# FOTA_LED_Driver.net
KiCad netlist of a schematic drawn in Altium Designer
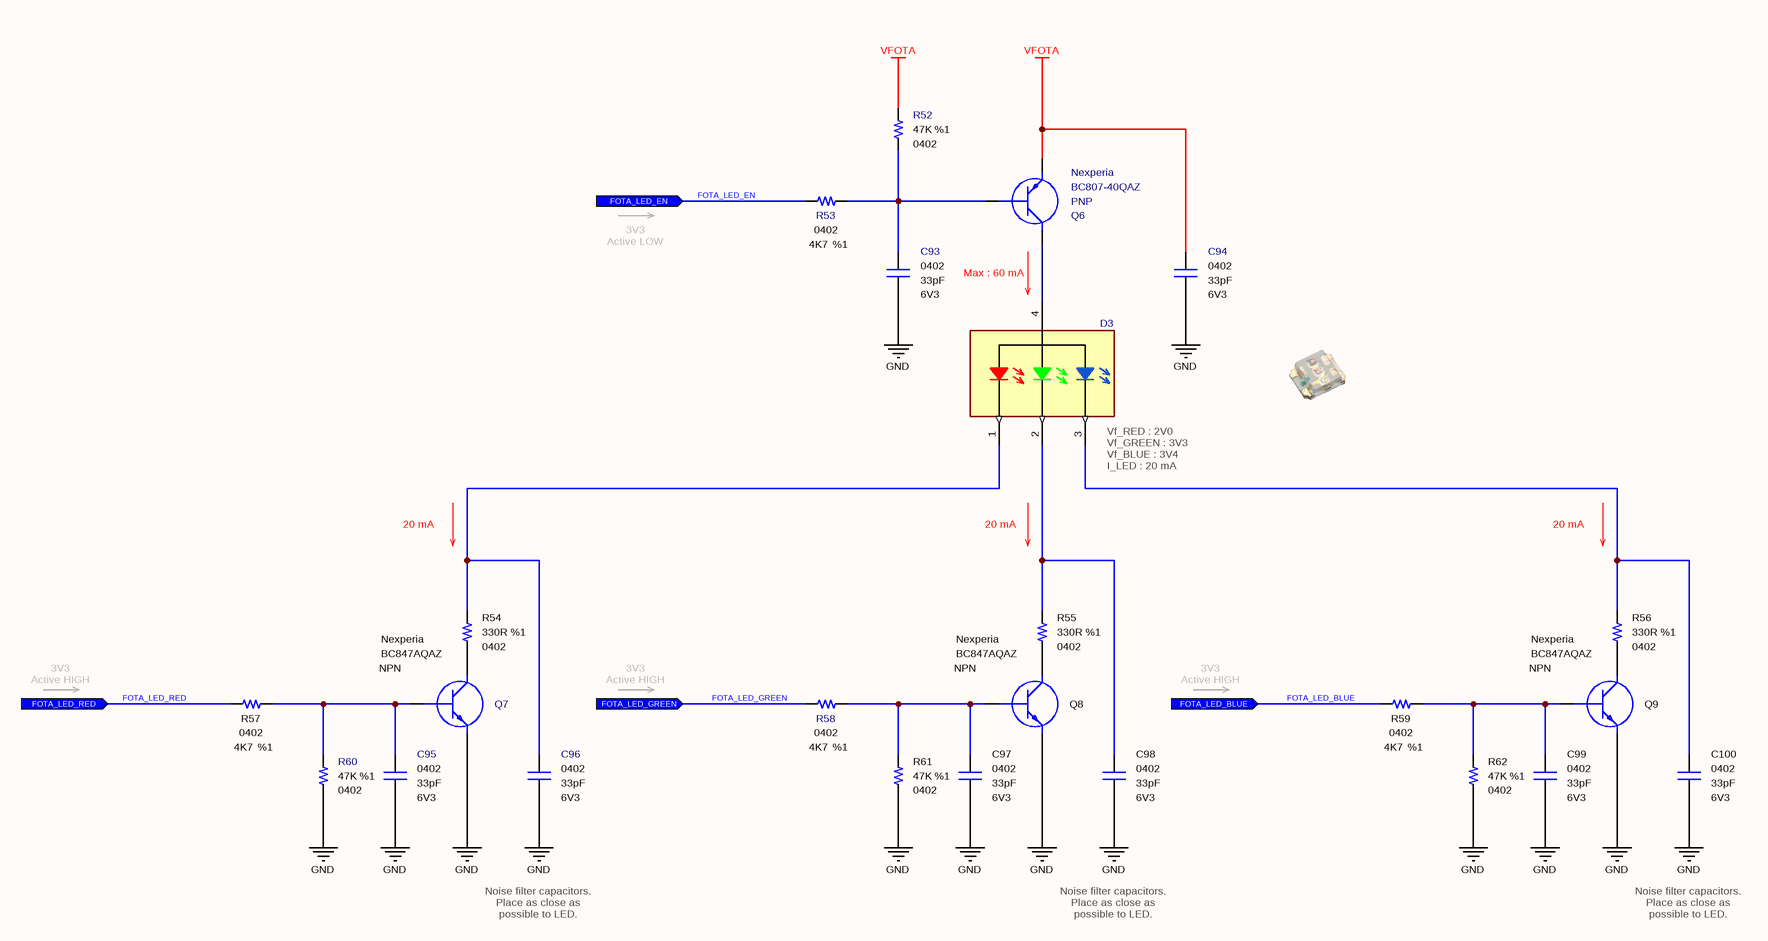
[diagram p0: FOTA LED Driver.SchDoc]

(export (version "E")
  (design (tool "Eeschema 10.0.6"))
  (components
    (comp (ref "C93")
      (value "33pF")
      (footprint "CAPACITOR_0402")
      (description "Capacitor - 33pF [0402] (Ceramic)")
      (fields
        (field (name "CASE") "0402")
        (field (name "TOLERANCE") "10%")
        (field (name "VOLTAGE") "6V3")
        (field (name "MANUFACTURER PART NUMBER") "C0402C330J9RACAUTO")
      )
      (libsource (lib "Ovoo_Library") (part "Capacitor - 33pF [0402-6V3]"))
    )
    (comp (ref "C94")
      (value "33pF")
      (footprint "CAPACITOR_0402")
      (description "Capacitor - 33pF [0402] (Ceramic)")
      (fields
        (field (name "CASE") "0402")
        (field (name "TOLERANCE") "10%")
        (field (name "VOLTAGE") "6V3")
        (field (name "MANUFACTURER PART NUMBER") "C0402C330J9RACAUTO")
      )
      (libsource (lib "Ovoo_Library") (part "Capacitor - 33pF [0402-6V3]"))
    )
    (comp (ref "C95")
      (value "33pF")
      (footprint "CAPACITOR_0402")
      (description "Capacitor - 33pF [0402] (Ceramic)")
      (fields
        (field (name "CASE") "0402")
        (field (name "TOLERANCE") "10%")
        (field (name "VOLTAGE") "6V3")
        (field (name "MANUFACTURER PART NUMBER") "C0402C330J9RACAUTO")
      )
      (libsource (lib "Ovoo_Library") (part "Capacitor - 33pF [0402-6V3]"))
    )
    (comp (ref "C96")
      (value "33pF")
      (footprint "CAPACITOR_0402")
      (description "Capacitor - 33pF [0402] (Ceramic)")
      (fields
        (field (name "CASE") "0402")
        (field (name "TOLERANCE") "10%")
        (field (name "VOLTAGE") "6V3")
        (field (name "MANUFACTURER PART NUMBER") "C0402C330J9RACAUTO")
      )
      (libsource (lib "Ovoo_Library") (part "Capacitor - 33pF [0402-6V3]"))
    )
    (comp (ref "C97")
      (value "33pF")
      (footprint "CAPACITOR_0402")
      (description "Capacitor - 33pF [0402] (Ceramic)")
      (fields
        (field (name "CASE") "0402")
        (field (name "TOLERANCE") "10%")
        (field (name "VOLTAGE") "6V3")
        (field (name "MANUFACTURER PART NUMBER") "C0402C330J9RACAUTO")
      )
      (libsource (lib "Ovoo_Library") (part "Capacitor - 33pF [0402-6V3]"))
    )
    (comp (ref "C98")
      (value "33pF")
      (footprint "CAPACITOR_0402")
      (description "Capacitor - 33pF [0402] (Ceramic)")
      (fields
        (field (name "CASE") "0402")
        (field (name "TOLERANCE") "10%")
        (field (name "VOLTAGE") "6V3")
        (field (name "MANUFACTURER PART NUMBER") "C0402C330J9RACAUTO")
      )
      (libsource (lib "Ovoo_Library") (part "Capacitor - 33pF [0402-6V3]"))
    )
    (comp (ref "C99")
      (value "33pF")
      (footprint "CAPACITOR_0402")
      (description "Capacitor - 33pF [0402] (Ceramic)")
      (fields
        (field (name "CASE") "0402")
        (field (name "TOLERANCE") "10%")
        (field (name "VOLTAGE") "6V3")
        (field (name "MANUFACTURER PART NUMBER") "C0402C330J9RACAUTO")
      )
      (libsource (lib "Ovoo_Library") (part "Capacitor - 33pF [0402-6V3]"))
    )
    (comp (ref "C100")
      (value "33pF")
      (footprint "CAPACITOR_0402")
      (description "Capacitor - 33pF [0402] (Ceramic)")
      (fields
        (field (name "CASE") "0402")
        (field (name "TOLERANCE") "10%")
        (field (name "VOLTAGE") "6V3")
        (field (name "MANUFACTURER PART NUMBER") "C0402C330J9RACAUTO")
      )
      (libsource (lib "Ovoo_Library") (part "Capacitor - 33pF [0402-6V3]"))
    )
    (comp (ref "D3")
      (value "150066M153000")
      (footprint "Wurth_0606")
      (description "Standard LEDs - SMD PICOLED series Red LED")
      (fields (field (name "MOUSER PART NUMBER") "710-150066M153000"))
      (libsource (lib "Ovoo_Library") (part "Diode - RGB LED (150066M153000)"))
    )
    (comp (ref "Q6")
      (value "Bipolar PNP Transistors")
      (footprint "SOT1215")
      (description "Bipolar Transistors - BJT 45 V, 500 mA PNP gen purpose transistors")
      (fields
        (field (name "MOUSER PART NUMBER") "771-BC807-40QAZ")
        (field (name "POLARITY") "PNP")
        (field (name "MANUFACTURER NAME") "Nexperia")
        (field (name "MANUFACTURER PART NUMBER") "BC807-40QAZ")
      )
      (libsource (lib "Ovoo_Library") (part "Transistor - BC807"))
    )
    (comp (ref "Q7")
      (value "BC847AQAZ")
      (footprint "SOT1215")
      (description "Bipolar NPN Transistors")
      (fields
        (field (name "POLARITY") "NPN")
        (field (name "MANUFACTURER NAME") "Nexperia")
        (field (name "MANUFACTURER PART NUMBER") "BC847AQAZ")
      )
      (libsource (lib "Ovoo_Library") (part "Transistor - BC847"))
    )
    (comp (ref "Q8")
      (value "BC847AQAZ")
      (footprint "SOT1215")
      (description "Bipolar NPN Transistors")
      (fields
        (field (name "POLARITY") "NPN")
        (field (name "MANUFACTURER NAME") "Nexperia")
        (field (name "MANUFACTURER PART NUMBER") "BC847AQAZ")
      )
      (libsource (lib "Ovoo_Library") (part "Transistor - BC847"))
    )
    (comp (ref "Q9")
      (value "BC847AQAZ")
      (footprint "SOT1215")
      (description "Bipolar NPN Transistors")
      (fields
        (field (name "POLARITY") "NPN")
        (field (name "MANUFACTURER NAME") "Nexperia")
        (field (name "MANUFACTURER PART NUMBER") "BC847AQAZ")
      )
      (libsource (lib "Ovoo_Library") (part "Transistor - BC847"))
    )
    (comp (ref "R52")
      (value "47K")
      (footprint "RESISTOR_0402")
      (description "Thick Film Resistors - SMD 1/16 W 47 Kohms 1%")
      (fields
        (field (name "TOLERANCE") "%1")
        (field (name "CASE") "0402")
        (field (name "MANUFACTURER PART NUMBER") "CRCW040247K0FKED")
        (field (name "Comment") "47K - 0402 - %1 - 1/16W")
      )
      (libsource (lib "Ovoo_Library") (part "Resistor - 47K"))
    )
    (comp (ref "R53")
      (value "4K7")
      (footprint "RESISTOR_0402")
      (description "Thick Film Resistors - SMD 1/16 W 4.7 Kohms 1%")
      (fields
        (field (name "MANUFACTURER PART NUMBER") "CRCW04024K70FKED")
        (field (name "MOUSER PART NUMBER") "71-CRCW0402-4.7K-E3")
        (field (name "TOLERANCE") "%1")
        (field (name "CASE") "0402")
      )
      (libsource (lib "Ovoo_Library") (part "Resistor - 4K7"))
    )
    (comp (ref "R54")
      (value "330R")
      (footprint "RESISTOR_0402")
      (description "Thick Film Resistors - SMD 1/16 W 330 Ohm 1%")
      (fields
        (field (name "MANUFACTURER PART NUMBER") "CRCW0402330RFKED")
        (field (name "MOUSER PART NUMBER") "71-CRCW0402-330-E3")
        (field (name "CASE") "0402")
        (field (name "TOLERANCE") "%1")
      )
      (libsource (lib "Ovoo_Library") (part "Resistor - 330R"))
    )
    (comp (ref "R55")
      (value "330R")
      (footprint "RESISTOR_0402")
      (description "Thick Film Resistors - SMD 1/16 W 330 Ohm 1%")
      (fields
        (field (name "MANUFACTURER PART NUMBER") "CRCW0402330RFKED")
        (field (name "MOUSER PART NUMBER") "71-CRCW0402-330-E3")
        (field (name "CASE") "0402")
        (field (name "TOLERANCE") "%1")
      )
      (libsource (lib "Ovoo_Library") (part "Resistor - 330R"))
    )
    (comp (ref "R56")
      (value "330R")
      (footprint "RESISTOR_0402")
      (description "Thick Film Resistors - SMD 1/16 W 330 Ohm 1%")
      (fields
        (field (name "MANUFACTURER PART NUMBER") "CRCW0402330RFKED")
        (field (name "MOUSER PART NUMBER") "71-CRCW0402-330-E3")
        (field (name "CASE") "0402")
        (field (name "TOLERANCE") "%1")
      )
      (libsource (lib "Ovoo_Library") (part "Resistor - 330R"))
    )
    (comp (ref "R57")
      (value "4K7")
      (footprint "RESISTOR_0402")
      (description "Thick Film Resistors - SMD 1/16 W 4.7 Kohms 1%")
      (fields
        (field (name "MANUFACTURER PART NUMBER") "CRCW04024K70FKED")
        (field (name "MOUSER PART NUMBER") "71-CRCW0402-4.7K-E3")
        (field (name "TOLERANCE") "%1")
        (field (name "CASE") "0402")
      )
      (libsource (lib "Ovoo_Library") (part "Resistor - 4K7"))
    )
    (comp (ref "R58")
      (value "4K7")
      (footprint "RESISTOR_0402")
      (description "Thick Film Resistors - SMD 1/16 W 4.7 Kohms 1%")
      (fields
        (field (name "MANUFACTURER PART NUMBER") "CRCW04024K70FKED")
        (field (name "MOUSER PART NUMBER") "71-CRCW0402-4.7K-E3")
        (field (name "TOLERANCE") "%1")
        (field (name "CASE") "0402")
      )
      (libsource (lib "Ovoo_Library") (part "Resistor - 4K7"))
    )
    (comp (ref "R59")
      (value "4K7")
      (footprint "RESISTOR_0402")
      (description "Thick Film Resistors - SMD 1/16 W 4.7 Kohms 1%")
      (fields
        (field (name "MANUFACTURER PART NUMBER") "CRCW04024K70FKED")
        (field (name "MOUSER PART NUMBER") "71-CRCW0402-4.7K-E3")
        (field (name "TOLERANCE") "%1")
        (field (name "CASE") "0402")
      )
      (libsource (lib "Ovoo_Library") (part "Resistor - 4K7"))
    )
    (comp (ref "R60")
      (value "47K")
      (footprint "RESISTOR_0402")
      (description "Thick Film Resistors - SMD 1/16 W 47 Kohms 1%")
      (fields
        (field (name "TOLERANCE") "%1")
        (field (name "CASE") "0402")
        (field (name "MANUFACTURER PART NUMBER") "CRCW040247K0FKED")
        (field (name "Comment") "47K - 0402 - %1 - 1/16W")
      )
      (libsource (lib "Ovoo_Library") (part "Resistor - 47K"))
    )
    (comp (ref "R61")
      (value "47K")
      (footprint "RESISTOR_0402")
      (description "Thick Film Resistors - SMD 1/16 W 47 Kohms 1%")
      (fields
        (field (name "TOLERANCE") "%1")
        (field (name "CASE") "0402")
        (field (name "MANUFACTURER PART NUMBER") "CRCW040247K0FKED")
        (field (name "Comment") "47K - 0402 - %1 - 1/16W")
      )
      (libsource (lib "Ovoo_Library") (part "Resistor - 47K"))
    )
    (comp (ref "R62")
      (value "47K")
      (footprint "RESISTOR_0402")
      (description "Thick Film Resistors - SMD 1/16 W 47 Kohms 1%")
      (fields
        (field (name "TOLERANCE") "%1")
        (field (name "CASE") "0402")
        (field (name "MANUFACTURER PART NUMBER") "CRCW040247K0FKED")
        (field (name "Comment") "47K - 0402 - %1 - 1/16W")
      )
      (libsource (lib "Ovoo_Library") (part "Resistor - 47K"))
    )
  )
  (nets
    (net (code "1") (name "/FOTA_LED_BLUE") (class "Default")
      (node (ref "R59") (pin "2") (pinfunction "2_2") (pintype "passive"))
    )
    (net (code "2") (name "/FOTA_LED_EN") (class "Default")
      (node (ref "R53") (pin "2") (pinfunction "2_2") (pintype "passive"))
    )
    (net (code "3") (name "/FOTA_LED_GREEN") (class "Default")
      (node (ref "R58") (pin "2") (pinfunction "2_2") (pintype "passive"))
    )
    (net (code "4") (name "/FOTA_LED_RED") (class "Default")
      (node (ref "R57") (pin "2") (pinfunction "2_2") (pintype "passive"))
    )
    (net (code "5") (name "GND") (class "Default")
      (node (ref "C100") (pin "2") (pinfunction "2_2") (pintype "passive"))
      (node (ref "C93") (pin "2") (pinfunction "2_2") (pintype "passive"))
      (node (ref "C94") (pin "2") (pinfunction "2_2") (pintype "passive"))
      (node (ref "C95") (pin "2") (pinfunction "2_2") (pintype "passive"))
      (node (ref "C96") (pin "2") (pinfunction "2_2") (pintype "passive"))
      (node (ref "C97") (pin "2") (pinfunction "2_2") (pintype "passive"))
      (node (ref "C98") (pin "2") (pinfunction "2_2") (pintype "passive"))
      (node (ref "C99") (pin "2") (pinfunction "2_2") (pintype "passive"))
      (node (ref "Q7") (pin "2") (pinfunction "E_2") (pintype "passive"))
      (node (ref "Q8") (pin "2") (pinfunction "E_2") (pintype "passive"))
      (node (ref "Q9") (pin "2") (pinfunction "E_2") (pintype "passive"))
      (node (ref "R60") (pin "1") (pinfunction "1_1") (pintype "passive"))
      (node (ref "R61") (pin "1") (pinfunction "1_1") (pintype "passive"))
      (node (ref "R62") (pin "1") (pinfunction "1_1") (pintype "passive"))
    )
    (net (code "6") (name "Net-(C96-Pad1)") (class "Default")
      (node (ref "C96") (pin "1") (pinfunction "1_1") (pintype "passive"))
      (node (ref "D3") (pin "1") (pinfunction "1_1") (pintype "output"))
      (node (ref "R54") (pin "2") (pinfunction "2_2") (pintype "passive"))
    )
    (net (code "7") (name "Net-(C98-Pad1)") (class "Default")
      (node (ref "C98") (pin "1") (pinfunction "1_1") (pintype "passive"))
      (node (ref "D3") (pin "2") (pinfunction "2_2") (pintype "output"))
      (node (ref "R55") (pin "2") (pinfunction "2_2") (pintype "passive"))
    )
    (net (code "8") (name "Net-(C100-Pad1)") (class "Default")
      (node (ref "C100") (pin "1") (pinfunction "1_1") (pintype "passive"))
      (node (ref "D3") (pin "3") (pinfunction "3_3") (pintype "output"))
      (node (ref "R56") (pin "2") (pinfunction "2_2") (pintype "passive"))
    )
    (net (code "9") (name "Net-(Q6-B)") (class "Default")
      (node (ref "C93") (pin "1") (pinfunction "1_1") (pintype "passive"))
      (node (ref "Q6") (pin "1") (pinfunction "B_1") (pintype "passive"))
      (node (ref "R52") (pin "1") (pinfunction "1_1") (pintype "passive"))
      (node (ref "R53") (pin "1") (pinfunction "1_1") (pintype "passive"))
    )
    (net (code "10") (name "Net-(Q6-C)") (class "Default")
      (node (ref "D3") (pin "4") (pinfunction "4_4") (pintype "power_in"))
      (node (ref "Q6") (pin "3") (pinfunction "C_3") (pintype "passive"))
    )
    (net (code "11") (name "Net-(Q7-B)") (class "Default")
      (node (ref "C95") (pin "1") (pinfunction "1_1") (pintype "passive"))
      (node (ref "Q7") (pin "1") (pinfunction "B_1") (pintype "passive"))
      (node (ref "R57") (pin "1") (pinfunction "1_1") (pintype "passive"))
      (node (ref "R60") (pin "2") (pinfunction "2_2") (pintype "passive"))
    )
    (net (code "12") (name "Net-(Q7-C)") (class "Default")
      (node (ref "Q7") (pin "3") (pinfunction "C_3") (pintype "passive"))
      (node (ref "R54") (pin "1") (pinfunction "1_1") (pintype "passive"))
    )
    (net (code "13") (name "Net-(Q8-B)") (class "Default")
      (node (ref "C97") (pin "1") (pinfunction "1_1") (pintype "passive"))
      (node (ref "Q8") (pin "1") (pinfunction "B_1") (pintype "passive"))
      (node (ref "R58") (pin "1") (pinfunction "1_1") (pintype "passive"))
      (node (ref "R61") (pin "2") (pinfunction "2_2") (pintype "passive"))
    )
    (net (code "14") (name "Net-(Q8-C)") (class "Default")
      (node (ref "Q8") (pin "3") (pinfunction "C_3") (pintype "passive"))
      (node (ref "R55") (pin "1") (pinfunction "1_1") (pintype "passive"))
    )
    (net (code "15") (name "Net-(Q9-B)") (class "Default")
      (node (ref "C99") (pin "1") (pinfunction "1_1") (pintype "passive"))
      (node (ref "Q9") (pin "1") (pinfunction "B_1") (pintype "passive"))
      (node (ref "R59") (pin "1") (pinfunction "1_1") (pintype "passive"))
      (node (ref "R62") (pin "2") (pinfunction "2_2") (pintype "passive"))
    )
    (net (code "16") (name "Net-(Q9-C)") (class "Default")
      (node (ref "Q9") (pin "3") (pinfunction "C_3") (pintype "passive"))
      (node (ref "R56") (pin "1") (pinfunction "1_1") (pintype "passive"))
    )
    (net (code "17") (name "VFOTA") (class "Default")
      (node (ref "C94") (pin "1") (pinfunction "1_1") (pintype "passive"))
      (node (ref "Q6") (pin "2") (pinfunction "E_2") (pintype "passive"))
      (node (ref "R52") (pin "2") (pinfunction "2_2") (pintype "passive"))
    )
  )
)
